# 04_Sensor.net
KiCad netlist of a schematic drawn in Altium Designer
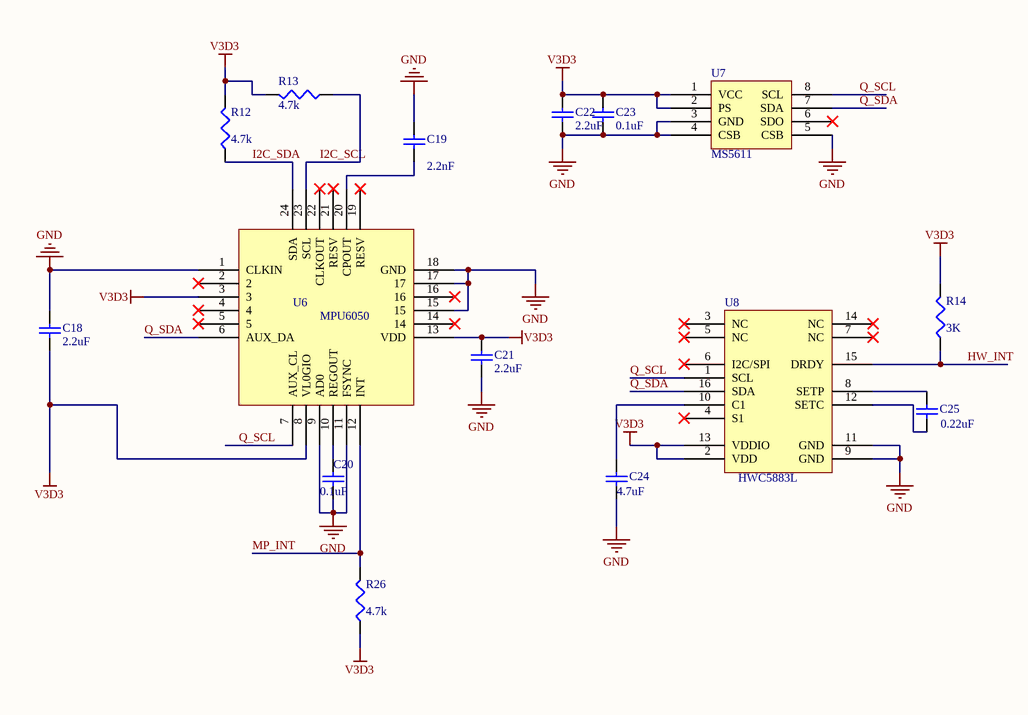
[diagram p0: 04_Sensor.SchDoc]

(export (version "E")
  (design (tool "Eeschema 10.0.6"))
  (components
    (comp (ref "C18")
      (value "2.2uF")
      (footprint "0402")
      (description "Capacitor")
      (fields (field (name "Comment") "Cap") (field (name "PUBLISHER") "Altium Limited"))
      (libsource (lib "Miscellaneous Devices") (part "Cap"))
    )
    (comp (ref "C19")
      (value "2.2nF")
      (footprint "0402")
      (description "Capacitor")
      (fields (field (name "Comment") "Cap") (field (name "PUBLISHER") "Altium Limited"))
      (libsource (lib "Miscellaneous Devices") (part "Cap"))
    )
    (comp (ref "C20")
      (value "0.1uF")
      (footprint "0402")
      (description "Capacitor")
      (fields (field (name "Comment") "Cap") (field (name "PUBLISHER") "Altium Limited"))
      (libsource (lib "Miscellaneous Devices") (part "Cap"))
    )
    (comp (ref "C21")
      (value "2.2uF")
      (footprint "0402")
      (description "Capacitor")
      (fields (field (name "Comment") "Cap") (field (name "PUBLISHER") "Altium Limited"))
      (libsource (lib "Miscellaneous Devices") (part "Cap"))
    )
    (comp (ref "C22")
      (value "2.2uF")
      (footprint "0402")
      (description "Capacitor")
      (fields (field (name "Comment") "Cap") (field (name "PUBLISHER") "Altium Limited"))
      (libsource (lib "Miscellaneous Devices") (part "Cap"))
    )
    (comp (ref "C23")
      (value "0.1uF")
      (footprint "0402")
      (description "Capacitor")
      (fields (field (name "Comment") "Cap") (field (name "PUBLISHER") "Altium Limited"))
      (libsource (lib "Miscellaneous Devices") (part "Cap"))
    )
    (comp (ref "C24")
      (value "4.7uF")
      (footprint "0402")
      (description "Capacitor")
      (fields (field (name "Comment") "Cap") (field (name "PUBLISHER") "Altium Limited"))
      (libsource (lib "Miscellaneous Devices") (part "Cap"))
    )
    (comp (ref "C25")
      (value "0.22uF")
      (footprint "0402")
      (description "Capacitor")
      (fields (field (name "Comment") "Cap") (field (name "PUBLISHER") "Altium Limited"))
      (libsource (lib "Miscellaneous Devices") (part "Cap"))
    )
    (comp (ref "R12")
      (value "4.7k")
      (footprint "0402")
      (description "Resistor")
      (fields (field (name "Comment") "Res3") (field (name "PUBLISHER") "Altium Limited"))
      (libsource (lib "Miscellaneous Devices") (part "Res3"))
    )
    (comp (ref "R13")
      (value "4.7k")
      (footprint "0402")
      (description "Resistor")
      (fields (field (name "Comment") "Res3") (field (name "PUBLISHER") "Altium Limited"))
      (libsource (lib "Miscellaneous Devices") (part "Res3"))
    )
    (comp (ref "R14")
      (value "3K")
      (footprint "0402")
      (description "Resistor")
      (fields (field (name "Comment") "Res3") (field (name "PUBLISHER") "Altium Limited"))
      (libsource (lib "Miscellaneous Devices") (part "Res3"))
    )
    (comp (ref "R26")
      (value "4.7k")
      (footprint "0402")
      (description "Resistor")
      (fields (field (name "Comment") "Res3") (field (name "PUBLISHER") "Altium Limited"))
      (libsource (lib "Miscellaneous Devices") (part "Res3"))
    )
    (comp (ref "U6")
      (value "MPU6050")
      (footprint "QFN24")
      (libsource (lib "aircraftschlib") (part "MPU6050"))
    )
    (comp (ref "U7")
      (value "MS5611")
      (footprint "MS5611 - duplicate")
      (libsource (lib "aircraftschlib") (part "MS5611"))
    )
    (comp (ref "U8")
      (value "HWC5883L")
      (footprint "HMC5883L")
      (libsource (lib "aircraftschlib") (part "HMC5883L"))
    )
  )
  (nets
    (net (code "1") (name "/HW_INT") (class "Default")
      (node (ref "R14") (pin "1") (pinfunction "1_1") (pintype "passive"))
      (node (ref "U8") (pin "15") (pinfunction "DRDY_15") (pintype "passive"))
    )
    (net (code "2") (name "/I2C_SCL") (class "Default")
      (node (ref "R13") (pin "1") (pinfunction "1_1") (pintype "passive"))
      (node (ref "U6") (pin "23") (pinfunction "SCL_23") (pintype "passive"))
    )
    (net (code "3") (name "/I2C_SDA") (class "Default")
      (node (ref "R12") (pin "1") (pinfunction "1_1") (pintype "passive"))
      (node (ref "U6") (pin "24") (pinfunction "SDA_24") (pintype "passive"))
    )
    (net (code "4") (name "/MP_INT") (class "Default")
      (node (ref "R26") (pin "2") (pinfunction "2_2") (pintype "passive"))
      (node (ref "U6") (pin "12") (pinfunction "INT_12") (pintype "passive"))
    )
    (net (code "5") (name "/Q_SCL") (class "Default")
      (node (ref "U6") (pin "7") (pinfunction "AUX_CL_7") (pintype "passive"))
      (node (ref "U7") (pin "8") (pinfunction "SCL_8") (pintype "passive"))
      (node (ref "U8") (pin "1") (pinfunction "SCL_1") (pintype "passive"))
    )
    (net (code "6") (name "/Q_SDA") (class "Default")
      (node (ref "U6") (pin "6") (pinfunction "AUX_DA_6") (pintype "passive"))
      (node (ref "U7") (pin "7") (pinfunction "SDA_7") (pintype "passive"))
      (node (ref "U8") (pin "16") (pinfunction "SDA_16") (pintype "passive"))
    )
    (net (code "7") (name "GND") (class "Default")
      (node (ref "C18") (pin "2") (pinfunction "2_2") (pintype "passive"))
      (node (ref "C19") (pin "2") (pinfunction "2_2") (pintype "passive"))
      (node (ref "C20") (pin "1") (pinfunction "1_1") (pintype "passive"))
      (node (ref "C21") (pin "1") (pinfunction "1_1") (pintype "passive"))
      (node (ref "C22") (pin "1") (pinfunction "1_1") (pintype "passive"))
      (node (ref "C23") (pin "1") (pinfunction "1_1") (pintype "passive"))
      (node (ref "C24") (pin "1") (pinfunction "1_1") (pintype "passive"))
      (node (ref "U6") (pin "1") (pinfunction "CLKIN_1") (pintype "passive"))
      (node (ref "U6") (pin "11") (pinfunction "FSYNC_11") (pintype "passive"))
      (node (ref "U6") (pin "15") (pinfunction "15_15") (pintype "passive"))
      (node (ref "U6") (pin "17") (pinfunction "17_17") (pintype "passive"))
      (node (ref "U6") (pin "18") (pinfunction "GND_18") (pintype "passive"))
      (node (ref "U6") (pin "9") (pinfunction "AD0_9") (pintype "passive"))
      (node (ref "U7") (pin "3") (pinfunction "GND_3") (pintype "passive"))
      (node (ref "U7") (pin "4") (pinfunction "CSB_4") (pintype "passive"))
      (node (ref "U7") (pin "5") (pinfunction "CSB_5") (pintype "passive"))
      (node (ref "U8") (pin "11") (pinfunction "GND_11") (pintype "passive"))
      (node (ref "U8") (pin "9") (pinfunction "GND_9") (pintype "passive"))
    )
    (net (code "8") (name "Net-(U6-CPOUT)") (class "Default")
      (node (ref "C19") (pin "1") (pinfunction "1_1") (pintype "passive"))
      (node (ref "U6") (pin "20") (pinfunction "CPOUT_20") (pintype "passive"))
    )
    (net (code "9") (name "Net-(U6-REGOUT)") (class "Default")
      (node (ref "C20") (pin "2") (pinfunction "2_2") (pintype "passive"))
      (node (ref "U6") (pin "10") (pinfunction "REGOUT_10") (pintype "passive"))
    )
    (net (code "10") (name "Net-(U8-C1)") (class "Default")
      (node (ref "C24") (pin "2") (pinfunction "2_2") (pintype "passive"))
      (node (ref "U8") (pin "10") (pinfunction "C1_10") (pintype "passive"))
    )
    (net (code "11") (name "Net-(U8-SETC)") (class "Default")
      (node (ref "C25") (pin "1") (pinfunction "1_1") (pintype "passive"))
      (node (ref "U8") (pin "12") (pinfunction "SETC_12") (pintype "passive"))
    )
    (net (code "12") (name "Net-(U8-SETP)") (class "Default")
      (node (ref "C25") (pin "2") (pinfunction "2_2") (pintype "passive"))
      (node (ref "U8") (pin "8") (pinfunction "SETP_8") (pintype "passive"))
    )
    (net (code "13") (name "V3D3") (class "Default")
      (node (ref "C18") (pin "1") (pinfunction "1_1") (pintype "passive"))
      (node (ref "C21") (pin "2") (pinfunction "2_2") (pintype "passive"))
      (node (ref "C22") (pin "2") (pinfunction "2_2") (pintype "passive"))
      (node (ref "C23") (pin "2") (pinfunction "2_2") (pintype "passive"))
      (node (ref "R12") (pin "2") (pinfunction "2_2") (pintype "passive"))
      (node (ref "R13") (pin "2") (pinfunction "2_2") (pintype "passive"))
      (node (ref "R14") (pin "2") (pinfunction "2_2") (pintype "passive"))
      (node (ref "R26") (pin "1") (pinfunction "1_1") (pintype "passive"))
      (node (ref "U6") (pin "13") (pinfunction "VDD_13") (pintype "passive"))
      (node (ref "U6") (pin "3") (pinfunction "3_3") (pintype "passive"))
      (node (ref "U6") (pin "8") (pinfunction "VL0GIO_8") (pintype "passive"))
      (node (ref "U7") (pin "1") (pinfunction "VCC_1") (pintype "passive"))
      (node (ref "U7") (pin "2") (pinfunction "PS_2") (pintype "passive"))
      (node (ref "U8") (pin "13") (pinfunction "VDDIO_13") (pintype "passive"))
      (node (ref "U8") (pin "2") (pinfunction "VDD_2") (pintype "passive"))
    )
    (net (code "14") (name "unconnected-(U6-CLKOUT-Pad22)") (class "Default")
      (node (ref "U6") (pin "22") (pinfunction "CLKOUT_22") (pintype "passive+no_connect"))
    )
    (net (code "15") (name "unconnected-(U6-Pad2)") (class "Default")
      (node (ref "U6") (pin "2") (pinfunction "2_2") (pintype "passive+no_connect"))
    )
    (net (code "16") (name "unconnected-(U6-Pad4)") (class "Default")
      (node (ref "U6") (pin "4") (pinfunction "4_4") (pintype "passive+no_connect"))
    )
    (net (code "17") (name "unconnected-(U6-Pad5)") (class "Default")
      (node (ref "U6") (pin "5") (pinfunction "5_5") (pintype "passive+no_connect"))
    )
    (net (code "18") (name "unconnected-(U6-Pad14)") (class "Default")
      (node (ref "U6") (pin "14") (pinfunction "14_14") (pintype "passive+no_connect"))
    )
    (net (code "19") (name "unconnected-(U6-Pad16)") (class "Default")
      (node (ref "U6") (pin "16") (pinfunction "16_16") (pintype "passive+no_connect"))
    )
    (net (code "20") (name "unconnected-(U6-RESV-Pad19)") (class "Default")
      (node (ref "U6") (pin "19") (pinfunction "RESV_19") (pintype "passive+no_connect"))
    )
    (net (code "21") (name "unconnected-(U6-RESV-Pad21)") (class "Default")
      (node (ref "U6") (pin "21") (pinfunction "RESV_21") (pintype "passive+no_connect"))
    )
    (net (code "22") (name "unconnected-(U7-SDO-Pad6)") (class "Default")
      (node (ref "U7") (pin "6") (pinfunction "SDO_6") (pintype "passive+no_connect"))
    )
    (net (code "23") (name "unconnected-(U8-I2C{slash}SPI-Pad6)") (class "Default")
      (node (ref "U8") (pin "6") (pinfunction "I2C/SPI_6") (pintype "passive+no_connect"))
    )
    (net (code "24") (name "unconnected-(U8-NC-Pad3)") (class "Default")
      (node (ref "U8") (pin "3") (pinfunction "NC_3") (pintype "passive+no_connect"))
    )
    (net (code "25") (name "unconnected-(U8-NC-Pad5)") (class "Default")
      (node (ref "U8") (pin "5") (pinfunction "NC_5") (pintype "passive+no_connect"))
    )
    (net (code "26") (name "unconnected-(U8-NC-Pad7)") (class "Default")
      (node (ref "U8") (pin "7") (pinfunction "NC_7") (pintype "passive+no_connect"))
    )
    (net (code "27") (name "unconnected-(U8-NC-Pad14)") (class "Default")
      (node (ref "U8") (pin "14") (pinfunction "NC_14") (pintype "passive+no_connect"))
    )
    (net (code "28") (name "unconnected-(U8-S1-Pad4)") (class "Default")
      (node (ref "U8") (pin "4") (pinfunction "S1_4") (pintype "passive+no_connect"))
    )
  )
)
